# Comms.net
KiCad netlist of a schematic drawn in Altium Designer
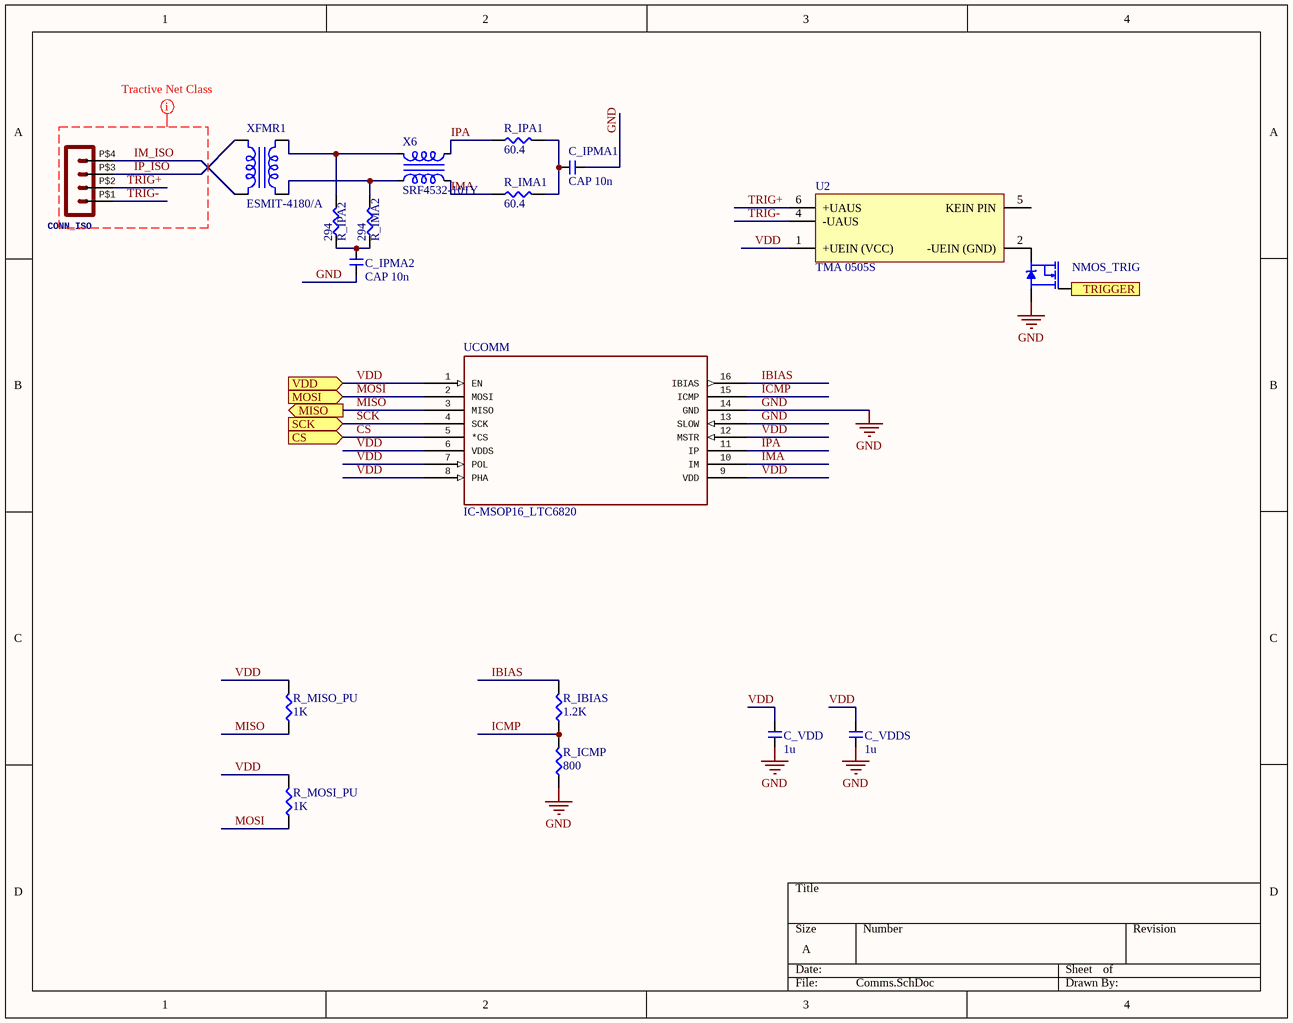
[diagram p0: Comms.SchDoc]

(export (version "E")
  (design (tool "Eeschema 10.0.6"))
  (components
    (comp (ref "CONN_ISO")
      (value "Molex - Micro-Fit 3.0 Series connector,  3.00mm (0.118\") pitch header, 4 positions.")
      (footprint "43650-0424")
      (libsource (lib "ife19_Elec_Conn_Library") (part "POS4_MF43650-0424"))
    )
    (comp (ref "C_IPMA1")
      (value "CAP 10n")
      (footprint "CAP-0603")
      (description "CAP-0603")
      (libsource (lib "ife18_TS_BMS_LTC6813_v2_Library") (part "CAP-0603"))
    )
    (comp (ref "C_IPMA2")
      (value "CAP 10n")
      (footprint "CAP-0603")
      (description "CAP-0603")
      (libsource (lib "ife18_TS_BMS_LTC6813_v2_Library") (part "CAP-0603"))
    )
    (comp (ref "C_VDD")
      (value "1u")
      (footprint "CAP-0603")
      (libsource (lib "altium-import") (part "root_1_CAP-0603_"))
    )
    (comp (ref "C_VDDS")
      (value "1u")
      (footprint "CAP-0603")
      (libsource (lib "altium-import") (part "root_1_CAP-0603_"))
    )
    (comp (ref "NMOS_TRIG")
      (value "NMOS-SOT23")
      (footprint "SOT23")
      (libsource (lib "altium-import") (part "root_0_NMOS-SOT23_"))
    )
    (comp (ref "R_IBIAS")
      (value "1.2K")
      (footprint "RES-0603")
      (libsource (lib "altium-import") (part "root_1_RES-0603_"))
    )
    (comp (ref "R_ICMP")
      (value "800")
      (footprint "RES-0603")
      (libsource (lib "altium-import") (part "root_1_RES-0603_"))
    )
    (comp (ref "R_IMA1")
      (value "60.4")
      (footprint "RES-0603")
      (libsource (lib "ife18_TS_BMS_LTC6813_v2_Library") (part "RES-0603"))
    )
    (comp (ref "R_IMA2")
      (value "294")
      (footprint "RES-0603")
      (libsource (lib "ife18_TS_BMS_LTC6813_v2_Library") (part "RES-0603"))
    )
    (comp (ref "R_IPA1")
      (value "60.4")
      (footprint "RES-0603")
      (libsource (lib "ife18_TS_BMS_LTC6813_v2_Library") (part "RES-0603"))
    )
    (comp (ref "R_IPA2")
      (value "294")
      (footprint "RES-0603")
      (libsource (lib "ife18_TS_BMS_LTC6813_v2_Library") (part "RES-0603"))
    )
    (comp (ref "R_MISO_PU")
      (value "1K")
      (footprint "RES-0603")
      (libsource (lib "altium-import") (part "root_1_RES-0603_"))
    )
    (comp (ref "R_MOSI_PU")
      (value "1K")
      (footprint "RES-0603")
      (libsource (lib "altium-import") (part "root_1_RES-0603_"))
    )
    (comp (ref "U2")
      (value "TMA 0505S")
      (footprint "TRACO-TMA0505S")
      (description "DC/DC Converter, 200 mA, 5 VDC, -40 to 85 degC, 5-Pin THD, RoHS")
      (fields (field (name "MANUFACTURER") "Tracopower"))
      (libsource (lib "Altium Content Vault") (part "TRACO-TMA0505S-5"))
    )
    (comp (ref "UCOMM")
      (value "IC-MSOP16_LTC6820")
      (footprint "MSOP16")
      (libsource (lib "altium-import") (part "root_0_IC-MSOP16_LTC6820_"))
    )
    (comp (ref "X6")
      (value "SRF4532-101Y")
      (footprint "SRF4532")
      (libsource (lib "ife19_Elec_Library") (part "CMC_SRF4532"))
    )
    (comp (ref "XFMR1")
      (value "ESMIT-4180/A")
      (footprint "ISOXFMR_ESMIT4180")
      (libsource (lib "ife19_Elec_Library") (part "ISOXFMR_ESMIT4180"))
    )
  )
  (nets
    (net (code "1") (name "/CS") (class "Default")
      (node (ref "UCOMM") (pin "5") (pinfunction "*CS_5") (pintype "passive"))
    )
    (net (code "2") (name "/IBIAS") (class "Default")
      (node (ref "R_IBIAS") (pin "2") (pinfunction "2_2") (pintype "passive"))
      (node (ref "UCOMM") (pin "16") (pinfunction "IBIAS_16") (pintype "output"))
    )
    (net (code "3") (name "/ICMP") (class "Default")
      (node (ref "R_IBIAS") (pin "1") (pinfunction "1_1") (pintype "passive"))
      (node (ref "R_ICMP") (pin "2") (pinfunction "2_2") (pintype "passive"))
      (node (ref "UCOMM") (pin "15") (pinfunction "ICMP_15") (pintype "passive"))
    )
    (net (code "4") (name "/IMA") (class "Default")
      (node (ref "R_IMA1") (pin "2") (pinfunction "2_2") (pintype "passive"))
      (node (ref "UCOMM") (pin "10") (pinfunction "IM_10") (pintype "passive"))
      (node (ref "X6") (pin "1") (pinfunction "1_1") (pintype "passive"))
    )
    (net (code "5") (name "/IM_ISO") (class "Default")
      (node (ref "CONN_ISO") (pin "P$4") (pinfunction "4_P$4") (pintype "passive"))
      (node (ref "XFMR1") (pin "1") (pinfunction "1_1") (pintype "passive"))
    )
    (net (code "6") (name "/IPA") (class "Default")
      (node (ref "R_IPA1") (pin "2") (pinfunction "2_2") (pintype "passive"))
      (node (ref "UCOMM") (pin "11") (pinfunction "IP_11") (pintype "passive"))
      (node (ref "X6") (pin "4") (pinfunction "4_4") (pintype "passive"))
    )
    (net (code "7") (name "/IP_ISO") (class "Default")
      (node (ref "CONN_ISO") (pin "P$3") (pinfunction "3_P$3") (pintype "passive"))
      (node (ref "XFMR1") (pin "2") (pinfunction "2_2") (pintype "passive"))
    )
    (net (code "8") (name "/MISO") (class "Default")
      (node (ref "R_MISO_PU") (pin "1") (pinfunction "1_1") (pintype "passive"))
      (node (ref "UCOMM") (pin "3") (pinfunction "MISO_3") (pintype "passive"))
    )
    (net (code "9") (name "/MOSI") (class "Default")
      (node (ref "R_MOSI_PU") (pin "1") (pinfunction "1_1") (pintype "passive"))
      (node (ref "UCOMM") (pin "2") (pinfunction "MOSI_2") (pintype "passive"))
    )
    (net (code "10") (name "/SCK") (class "Default")
      (node (ref "UCOMM") (pin "4") (pinfunction "SCK_4") (pintype "passive"))
    )
    (net (code "11") (name "/TRIG+") (class "Default")
      (node (ref "CONN_ISO") (pin "P$2") (pinfunction "2_P$2") (pintype "passive"))
      (node (ref "U2") (pin "6") (pinfunction "+UAUS_6") (pintype "passive"))
    )
    (net (code "12") (name "/TRIG-") (class "Default")
      (node (ref "CONN_ISO") (pin "P$1") (pinfunction "1_P$1") (pintype "passive"))
      (node (ref "U2") (pin "4") (pinfunction "-UAUS_4") (pintype "passive"))
    )
    (net (code "13") (name "/TRIGGER") (class "Default")
      (node (ref "NMOS_TRIG") (pin "1") (pinfunction "G_1") (pintype "passive"))
    )
    (net (code "14") (name "/VDD") (class "Default")
      (node (ref "C_VDD") (pin "2") (pinfunction "2_2") (pintype "passive"))
      (node (ref "C_VDDS") (pin "2") (pinfunction "2_2") (pintype "passive"))
      (node (ref "R_MISO_PU") (pin "2") (pinfunction "2_2") (pintype "passive"))
      (node (ref "R_MOSI_PU") (pin "2") (pinfunction "2_2") (pintype "passive"))
      (node (ref "U2") (pin "1") (pinfunction "+UEIN_(VCC)_1") (pintype "power_in"))
      (node (ref "UCOMM") (pin "1") (pinfunction "EN_1") (pintype "input"))
      (node (ref "UCOMM") (pin "12") (pinfunction "MSTR_12") (pintype "input"))
      (node (ref "UCOMM") (pin "6") (pinfunction "VDDS_6") (pintype "power_in"))
      (node (ref "UCOMM") (pin "7") (pinfunction "POL_7") (pintype "input"))
      (node (ref "UCOMM") (pin "8") (pinfunction "PHA_8") (pintype "input"))
      (node (ref "UCOMM") (pin "9") (pinfunction "VDD_9") (pintype "power_in"))
    )
    (net (code "15") (name "GND") (class "Default")
      (node (ref "C_IPMA1") (pin "1") (pinfunction "1_1") (pintype "passive"))
      (node (ref "C_IPMA2") (pin "1") (pinfunction "1_1") (pintype "passive"))
      (node (ref "C_VDD") (pin "1") (pinfunction "1_1") (pintype "passive"))
      (node (ref "C_VDDS") (pin "1") (pinfunction "1_1") (pintype "passive"))
      (node (ref "NMOS_TRIG") (pin "2") (pinfunction "S_2") (pintype "passive"))
      (node (ref "R_ICMP") (pin "1") (pinfunction "1_1") (pintype "passive"))
      (node (ref "UCOMM") (pin "13") (pinfunction "SLOW_13") (pintype "input"))
      (node (ref "UCOMM") (pin "14") (pinfunction "GND_14") (pintype "power_in"))
    )
    (net (code "16") (name "Net-(C_IPMA1-Pad2)") (class "Default")
      (node (ref "C_IPMA1") (pin "2") (pinfunction "2_2") (pintype "passive"))
      (node (ref "R_IMA1") (pin "1") (pinfunction "1_1") (pintype "passive"))
      (node (ref "R_IPA1") (pin "1") (pinfunction "1_1") (pintype "passive"))
    )
    (net (code "17") (name "Net-(C_IPMA2-Pad2)") (class "Default")
      (node (ref "C_IPMA2") (pin "2") (pinfunction "2_2") (pintype "passive"))
      (node (ref "R_IMA2") (pin "1") (pinfunction "1_1") (pintype "passive"))
      (node (ref "R_IPA2") (pin "1") (pinfunction "1_1") (pintype "passive"))
    )
    (net (code "18") (name "Net-(NMOS_TRIG-D)") (class "Default")
      (node (ref "NMOS_TRIG") (pin "3") (pinfunction "D_3") (pintype "passive"))
      (node (ref "U2") (pin "2") (pinfunction "-UEIN_(GND)_2") (pintype "power_in"))
    )
    (net (code "19") (name "Net-(R_IMA2-Pad2)") (class "Default")
      (node (ref "R_IMA2") (pin "2") (pinfunction "2_2") (pintype "passive"))
      (node (ref "X6") (pin "2") (pinfunction "2_2") (pintype "passive"))
      (node (ref "XFMR1") (pin "4") (pinfunction "4_4") (pintype "passive"))
    )
    (net (code "20") (name "Net-(R_IPA2-Pad2)") (class "Default")
      (node (ref "R_IPA2") (pin "2") (pinfunction "2_2") (pintype "passive"))
      (node (ref "X6") (pin "3") (pinfunction "3_3") (pintype "passive"))
      (node (ref "XFMR1") (pin "3") (pinfunction "3_3") (pintype "passive"))
    )
    (net (code "21") (name "unconnected-(U2-KEIN_PIN-Pad5)") (class "Default")
      (node (ref "U2") (pin "5") (pinfunction "KEIN_PIN_5") (pintype "passive"))
    )
  )
)
